# ORD_FV1_2.net
KiCad netlist of a schematic drawn in Altium Designer
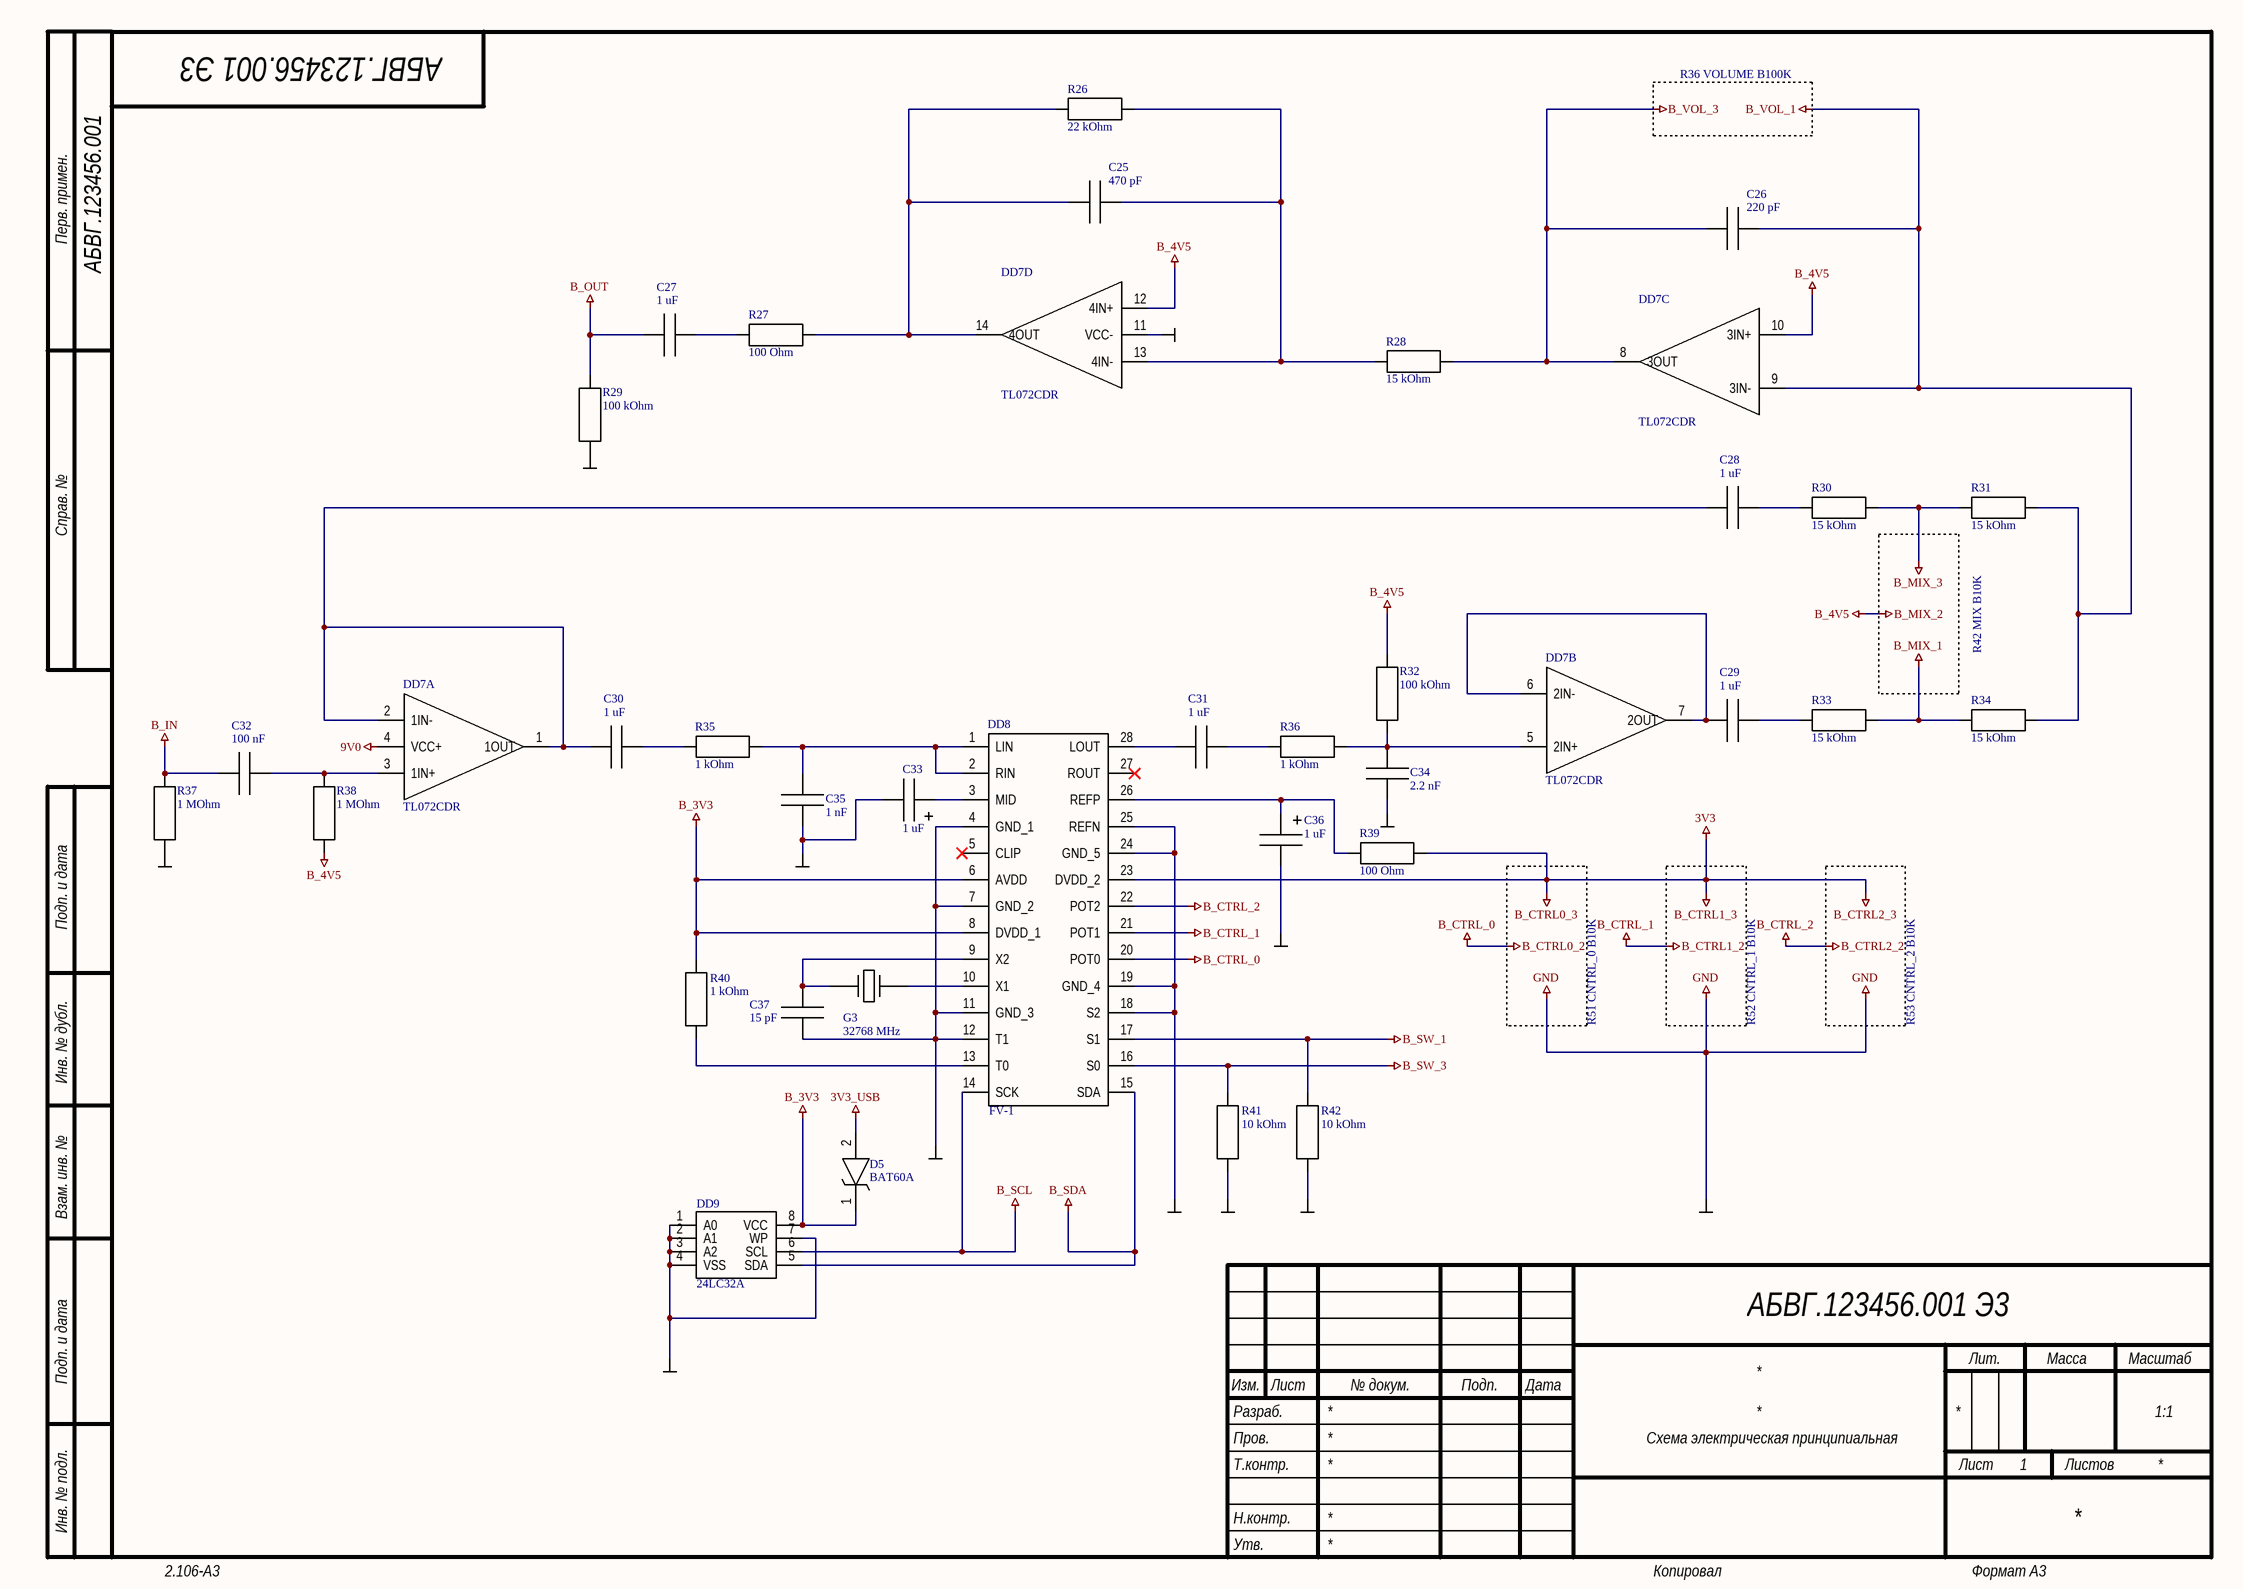
[diagram p0: ORD_FV1_2.SchDoc]

(export (version "E")
  (design (tool "Eeschema 10.0.6"))
  (components
    (comp (ref "C25")
      (value "470 pF")
      (footprint "C0805[2012]")
      (libsource (lib "Gost_passive_lib") (part "Capacitor"))
    )
    (comp (ref "C26")
      (value "220 pF")
      (footprint "C0805[2012]")
      (libsource (lib "Gost_passive_lib") (part "Capacitor"))
    )
    (comp (ref "C27")
      (value "1 uF")
      (footprint "C0805[2012]")
      (libsource (lib "Gost_passive_lib") (part "Capacitor"))
    )
    (comp (ref "C28")
      (value "1 uF")
      (footprint "C0805[2012]")
      (libsource (lib "Gost_passive_lib") (part "Capacitor"))
    )
    (comp (ref "C29")
      (value "1 uF")
      (footprint "C0805[2012]")
      (libsource (lib "Gost_passive_lib") (part "Capacitor"))
    )
    (comp (ref "C30")
      (value "1 uF")
      (footprint "C0805[2012]")
      (libsource (lib "Gost_passive_lib") (part "Capacitor"))
    )
    (comp (ref "C31")
      (value "1 uF")
      (footprint "C0805[2012]")
      (libsource (lib "Gost_passive_lib") (part "Capacitor"))
    )
    (comp (ref "C32")
      (value "100 nF")
      (footprint "C0805[2012]")
      (libsource (lib "Gost_passive_lib") (part "Capacitor"))
    )
    (comp (ref "C33")
      (value "1 uF")
      (footprint "C3216_CASE-A")
      (libsource (lib "Gost_passive_lib") (part "Capacitor_Pol"))
    )
    (comp (ref "C34")
      (value "2.2 nF")
      (footprint "C0805[2012]")
      (libsource (lib "Gost_passive_lib") (part "Capacitor"))
    )
    (comp (ref "C35")
      (value "1 nF")
      (footprint "C0805[2012]")
      (libsource (lib "Gost_passive_lib") (part "Capacitor"))
    )
    (comp (ref "C36")
      (value "1 uF")
      (footprint "C3216_CASE-A")
      (libsource (lib "Gost_passive_lib") (part "Capacitor_Pol"))
    )
    (comp (ref "C37")
      (value "15 pF")
      (footprint "C0805[2012]")
      (libsource (lib "Gost_passive_lib") (part "Capacitor"))
    )
    (comp (ref "D5")
      (value "BAT60A")
      (footprint "SOD323")
      (description "Diode Schottky 10V 3A Automotive 2-Pin SOD-323 T/R")
      (libsource (lib "Gost_passive_lib") (part "BAT60A"))
    )
    (comp (ref "DD7")
      (value "TL072CDR")
      (footprint "SO14")
      (description "TL072CDR, Dual Operational Amplifier 4 MHz -18 to 18V, 8-Pin SO")
      (fields
        (field (name "MANUFACTURER_PART_NUMBER") "LM358DT")
        (field (name "MOUSER PART NUMBER") "511-LM358DT")
      )
      (libsource (lib "Gost_active_libs") (part "TL074CDT"))
    )
    (comp (ref "DD8")
      (value "FV-1")
      (footprint "SOIC28")
      (description "FV-1 Reverb IC, Integrated Stereo ADC & DAC, Integrated Circuit, SOIC-28 300 MIL")
      (fields (field (name "MANUFACTURER_PART_NUMBER") "FV-1 Reverb IC"))
      (libsource (lib "Gost_active_libs") (part "FV-1"))
    )
    (comp (ref "DD9")
      (value "24LC32A")
      (footprint "DIP8_WITH_SOCKET")
      (description "32K I2C Serial EEPROM with Quarter-Array Write-Protect")
      (fields
        (field (name "MANUFACTURER_PART_NUMBER") "24LC32AF-I/P")
        (field (name "MOUSER PART NUMBER") "579-24LC32AF-I/P")
      )
      (libsource (lib "Gost_active_libs") (part "24LC32A"))
    )
    (comp (ref "G3")
      (value "32768 MHz")
      (footprint "HC-49")
      (libsource (lib "Gost_passive_lib") (part "Crystal_2pin"))
    )
    (comp (ref "R26")
      (value "22 kOhm")
      (footprint "R0805[2012]")
      (libsource (lib "Gost_passive_lib") (part "Resistor"))
    )
    (comp (ref "R27")
      (value "100 Ohm")
      (footprint "R0805[2012]")
      (libsource (lib "Gost_passive_lib") (part "Resistor"))
    )
    (comp (ref "R28")
      (value "15 kOhm")
      (footprint "R0805[2012]")
      (libsource (lib "Gost_passive_lib") (part "Resistor"))
    )
    (comp (ref "R29")
      (value "100 kOhm")
      (footprint "R0805[2012]")
      (libsource (lib "Gost_passive_lib") (part "Resistor"))
    )
    (comp (ref "R30")
      (value "15 kOhm")
      (footprint "R0805[2012]")
      (libsource (lib "Gost_passive_lib") (part "Resistor"))
    )
    (comp (ref "R31")
      (value "15 kOhm")
      (footprint "R0805[2012]")
      (libsource (lib "Gost_passive_lib") (part "Resistor"))
    )
    (comp (ref "R32")
      (value "100 kOhm")
      (footprint "R0805[2012]")
      (libsource (lib "Gost_passive_lib") (part "Resistor"))
    )
    (comp (ref "R33")
      (value "15 kOhm")
      (footprint "R0805[2012]")
      (libsource (lib "Gost_passive_lib") (part "Resistor"))
    )
    (comp (ref "R34")
      (value "15 kOhm")
      (footprint "R0805[2012]")
      (libsource (lib "Gost_passive_lib") (part "Resistor"))
    )
    (comp (ref "R35")
      (value "1 kOhm")
      (footprint "R0805[2012]")
      (libsource (lib "Gost_passive_lib") (part "Resistor"))
    )
    (comp (ref "R36")
      (value "1 kOhm")
      (footprint "R0805[2012]")
      (libsource (lib "Gost_passive_lib") (part "Resistor"))
    )
    (comp (ref "R37")
      (value "1 MOhm")
      (footprint "R0805[2012]")
      (libsource (lib "Gost_passive_lib") (part "Resistor"))
    )
    (comp (ref "R38")
      (value "1 MOhm")
      (footprint "R0805[2012]")
      (libsource (lib "Gost_passive_lib") (part "Resistor"))
    )
    (comp (ref "R39")
      (value "100 Ohm")
      (footprint "R0805[2012]")
      (libsource (lib "Gost_passive_lib") (part "Resistor"))
    )
    (comp (ref "R40")
      (value "1 kOhm")
      (footprint "R0805[2012]")
      (libsource (lib "Gost_passive_lib") (part "Resistor"))
    )
    (comp (ref "R41")
      (value "10 kOhm")
      (footprint "R0805[2012]")
      (libsource (lib "Gost_passive_lib") (part "Resistor"))
    )
    (comp (ref "R42")
      (value "10 kOhm")
      (footprint "R0805[2012]")
      (libsource (lib "Gost_passive_lib") (part "Resistor"))
    )
  )
  (nets
    (net (code "1") (name "3V3") (class "Default")
      (node (ref "DD8") (pin "23") (pinfunction "DVDD_2_23") (pintype "passive"))
      (node (ref "R39") (pin "1") (pinfunction "1_1") (pintype "passive"))
    )
    (net (code "2") (name "3V3_USB") (class "Default")
      (node (ref "D5") (pin "2") (pinfunction "A_2") (pintype "passive"))
    )
    (net (code "3") (name "9V0") (class "Default")
      (node (ref "DD7") (pin "4") (pinfunction "VCC+_4") (pintype "power_in"))
    )
    (net (code "4") (name "B_3V3") (class "Default")
      (node (ref "D5") (pin "1") (pinfunction "K_1") (pintype "passive"))
      (node (ref "DD8") (pin "6") (pinfunction "AVDD_6") (pintype "passive"))
      (node (ref "DD8") (pin "8") (pinfunction "DVDD_1_8") (pintype "passive"))
      (node (ref "DD9") (pin "8") (pinfunction "VCC_8") (pintype "passive"))
      (node (ref "R40") (pin "2") (pinfunction "2_2") (pintype "passive"))
    )
    (net (code "5") (name "B_4V5") (class "Default")
      (node (ref "DD7") (pin "10") (pinfunction "3IN+_10") (pintype "passive"))
      (node (ref "DD7") (pin "12") (pinfunction "4IN+_12") (pintype "passive"))
      (node (ref "R32") (pin "1") (pinfunction "1_1") (pintype "passive"))
      (node (ref "R38") (pin "1") (pinfunction "1_1") (pintype "passive"))
    )
    (net (code "6") (name "B_CTRL0_2") (class "Default")
      (node (ref "DD8") (pin "20") (pinfunction "POT0_20") (pintype "passive"))
    )
    (net (code "7") (name "B_CTRL1_2") (class "Default")
      (node (ref "DD8") (pin "21") (pinfunction "POT1_21") (pintype "passive"))
    )
    (net (code "8") (name "B_CTRL2_2") (class "Default")
      (node (ref "DD8") (pin "22") (pinfunction "POT2_22") (pintype "passive"))
    )
    (net (code "9") (name "B_IN") (class "Default")
      (node (ref "C32") (pin "1") (pinfunction "1_1") (pintype "passive"))
      (node (ref "R37") (pin "2") (pinfunction "2_2") (pintype "passive"))
    )
    (net (code "10") (name "B_MIX_1") (class "Default")
      (node (ref "R33") (pin "1") (pinfunction "1_1") (pintype "passive"))
      (node (ref "R34") (pin "2") (pinfunction "2_2") (pintype "passive"))
    )
    (net (code "11") (name "B_MIX_3") (class "Default")
      (node (ref "R30") (pin "1") (pinfunction "1_1") (pintype "passive"))
      (node (ref "R31") (pin "2") (pinfunction "2_2") (pintype "passive"))
    )
    (net (code "12") (name "B_OUT") (class "Default")
      (node (ref "C27") (pin "1") (pinfunction "1_1") (pintype "passive"))
      (node (ref "R29") (pin "2") (pinfunction "2_2") (pintype "passive"))
    )
    (net (code "13") (name "B_SCL") (class "Default")
      (node (ref "DD8") (pin "14") (pinfunction "SCK_14") (pintype "passive"))
      (node (ref "DD9") (pin "6") (pinfunction "SCL_6") (pintype "passive"))
    )
    (net (code "14") (name "B_SDA") (class "Default")
      (node (ref "DD8") (pin "15") (pinfunction "SDA_15") (pintype "passive"))
      (node (ref "DD9") (pin "5") (pinfunction "SDA_5") (pintype "passive"))
    )
    (net (code "15") (name "B_SW_1") (class "Default")
      (node (ref "DD8") (pin "17") (pinfunction "S1_17") (pintype "passive"))
      (node (ref "R42") (pin "2") (pinfunction "2_2") (pintype "passive"))
    )
    (net (code "16") (name "B_SW_3") (class "Default")
      (node (ref "DD8") (pin "16") (pinfunction "S0_16") (pintype "passive"))
      (node (ref "R41") (pin "2") (pinfunction "2_2") (pintype "passive"))
    )
    (net (code "17") (name "B_VOL_1") (class "Default")
      (node (ref "C26") (pin "2") (pinfunction "2_2") (pintype "passive"))
      (node (ref "DD7") (pin "9") (pinfunction "3IN-_9") (pintype "passive"))
      (node (ref "R31") (pin "1") (pinfunction "1_1") (pintype "passive"))
      (node (ref "R34") (pin "1") (pinfunction "1_1") (pintype "passive"))
    )
    (net (code "18") (name "B_VOL_3") (class "Default")
      (node (ref "C26") (pin "1") (pinfunction "1_1") (pintype "passive"))
      (node (ref "DD7") (pin "8") (pinfunction "3OUT_8") (pintype "passive"))
      (node (ref "R28") (pin "1") (pinfunction "1_1") (pintype "passive"))
    )
    (net (code "19") (name "GND") (class "Default")
      (node (ref "C33") (pin "2") (pinfunction "2_2") (pintype "passive"))
      (node (ref "C34") (pin "1") (pinfunction "1_1") (pintype "passive"))
      (node (ref "C35") (pin "1") (pinfunction "1_1") (pintype "passive"))
      (node (ref "C36") (pin "2") (pinfunction "2_2") (pintype "passive"))
      (node (ref "C37") (pin "2") (pinfunction "2_2") (pintype "passive"))
      (node (ref "DD7") (pin "11") (pinfunction "VCC-_11") (pintype "power_in"))
      (node (ref "DD8") (pin "11") (pinfunction "GND_3_11") (pintype "passive"))
      (node (ref "DD8") (pin "12") (pinfunction "T1_12") (pintype "passive"))
      (node (ref "DD8") (pin "18") (pinfunction "S2_18") (pintype "passive"))
      (node (ref "DD8") (pin "19") (pinfunction "GND_4_19") (pintype "passive"))
      (node (ref "DD8") (pin "24") (pinfunction "GND_5_24") (pintype "passive"))
      (node (ref "DD8") (pin "25") (pinfunction "REFN_25") (pintype "passive"))
      (node (ref "DD8") (pin "4") (pinfunction "GND_1_4") (pintype "passive"))
      (node (ref "DD8") (pin "7") (pinfunction "GND_2_7") (pintype "passive"))
      (node (ref "DD9") (pin "1") (pinfunction "A0_1") (pintype "passive"))
      (node (ref "DD9") (pin "2") (pinfunction "A1_2") (pintype "passive"))
      (node (ref "DD9") (pin "3") (pinfunction "A2_3") (pintype "passive"))
      (node (ref "DD9") (pin "4") (pinfunction "VSS_4") (pintype "passive"))
      (node (ref "DD9") (pin "7") (pinfunction "WP_7") (pintype "passive"))
      (node (ref "R29") (pin "1") (pinfunction "1_1") (pintype "passive"))
      (node (ref "R37") (pin "1") (pinfunction "1_1") (pintype "passive"))
      (node (ref "R41") (pin "1") (pinfunction "1_1") (pintype "passive"))
      (node (ref "R42") (pin "1") (pinfunction "1_1") (pintype "passive"))
    )
    (net (code "20") (name "Net-(C27-Pad2)") (class "Default")
      (node (ref "C27") (pin "2") (pinfunction "2_2") (pintype "passive"))
      (node (ref "R27") (pin "2") (pinfunction "2_2") (pintype "passive"))
    )
    (net (code "21") (name "Net-(C28-Pad2)") (class "Default")
      (node (ref "C28") (pin "2") (pinfunction "2_2") (pintype "passive"))
      (node (ref "R30") (pin "2") (pinfunction "2_2") (pintype "passive"))
    )
    (net (code "22") (name "Net-(C29-Pad2)") (class "Default")
      (node (ref "C29") (pin "2") (pinfunction "2_2") (pintype "passive"))
      (node (ref "R33") (pin "2") (pinfunction "2_2") (pintype "passive"))
    )
    (net (code "23") (name "Net-(C30-Pad2)") (class "Default")
      (node (ref "C30") (pin "2") (pinfunction "2_2") (pintype "passive"))
      (node (ref "R35") (pin "2") (pinfunction "2_2") (pintype "passive"))
    )
    (net (code "24") (name "Net-(C31-Pad2)") (class "Default")
      (node (ref "C31") (pin "2") (pinfunction "2_2") (pintype "passive"))
      (node (ref "R36") (pin "2") (pinfunction "2_2") (pintype "passive"))
    )
    (net (code "25") (name "Net-(DD7A-1IN+)") (class "Default")
      (node (ref "C32") (pin "2") (pinfunction "2_2") (pintype "passive"))
      (node (ref "DD7") (pin "3") (pinfunction "1IN+_3") (pintype "passive"))
      (node (ref "R38") (pin "2") (pinfunction "2_2") (pintype "passive"))
    )
    (net (code "26") (name "Net-(DD7A-1IN-)") (class "Default")
      (node (ref "C28") (pin "1") (pinfunction "1_1") (pintype "passive"))
      (node (ref "C30") (pin "1") (pinfunction "1_1") (pintype "passive"))
      (node (ref "DD7") (pin "1") (pinfunction "1OUT_1") (pintype "passive"))
      (node (ref "DD7") (pin "2") (pinfunction "1IN-_2") (pintype "passive"))
    )
    (net (code "27") (name "Net-(DD7B-2IN+)") (class "Default")
      (node (ref "C34") (pin "2") (pinfunction "2_2") (pintype "passive"))
      (node (ref "DD7") (pin "5") (pinfunction "2IN+_5") (pintype "passive"))
      (node (ref "R32") (pin "2") (pinfunction "2_2") (pintype "passive"))
      (node (ref "R36") (pin "1") (pinfunction "1_1") (pintype "passive"))
    )
    (net (code "28") (name "Net-(DD7B-2IN-)") (class "Default")
      (node (ref "C29") (pin "1") (pinfunction "1_1") (pintype "passive"))
      (node (ref "DD7") (pin "6") (pinfunction "2IN-_6") (pintype "passive"))
      (node (ref "DD7") (pin "7") (pinfunction "2OUT_7") (pintype "passive"))
    )
    (net (code "29") (name "Net-(DD7D-4IN-)") (class "Default")
      (node (ref "C25") (pin "2") (pinfunction "2_2") (pintype "passive"))
      (node (ref "DD7") (pin "13") (pinfunction "4IN-_13") (pintype "passive"))
      (node (ref "R26") (pin "1") (pinfunction "1_1") (pintype "passive"))
      (node (ref "R28") (pin "2") (pinfunction "2_2") (pintype "passive"))
    )
    (net (code "30") (name "Net-(DD7D-4OUT)") (class "Default")
      (node (ref "C25") (pin "1") (pinfunction "1_1") (pintype "passive"))
      (node (ref "DD7") (pin "14") (pinfunction "4OUT_14") (pintype "passive"))
      (node (ref "R26") (pin "2") (pinfunction "2_2") (pintype "passive"))
      (node (ref "R27") (pin "1") (pinfunction "1_1") (pintype "passive"))
    )
    (net (code "31") (name "Net-(DD8-LIN)") (class "Default")
      (node (ref "C35") (pin "2") (pinfunction "2_2") (pintype "passive"))
      (node (ref "DD8") (pin "1") (pinfunction "LIN_1") (pintype "passive"))
      (node (ref "DD8") (pin "2") (pinfunction "RIN_2") (pintype "passive"))
      (node (ref "R35") (pin "1") (pinfunction "1_1") (pintype "passive"))
    )
    (net (code "32") (name "Net-(DD8-LOUT)") (class "Default")
      (node (ref "C31") (pin "1") (pinfunction "1_1") (pintype "passive"))
      (node (ref "DD8") (pin "28") (pinfunction "LOUT_28") (pintype "passive"))
    )
    (net (code "33") (name "Net-(DD8-MID)") (class "Default")
      (node (ref "C33") (pin "1") (pinfunction "1_1") (pintype "passive"))
      (node (ref "DD8") (pin "3") (pinfunction "MID_3") (pintype "passive"))
    )
    (net (code "34") (name "Net-(DD8-REFP)") (class "Default")
      (node (ref "C36") (pin "1") (pinfunction "1_1") (pintype "passive"))
      (node (ref "DD8") (pin "26") (pinfunction "REFP_26") (pintype "passive"))
      (node (ref "R39") (pin "2") (pinfunction "2_2") (pintype "passive"))
    )
    (net (code "35") (name "Net-(DD8-T0)") (class "Default")
      (node (ref "DD8") (pin "13") (pinfunction "T0_13") (pintype "passive"))
      (node (ref "R40") (pin "1") (pinfunction "1_1") (pintype "passive"))
    )
    (net (code "36") (name "Net-(DD8-X1)") (class "Default")
      (node (ref "DD8") (pin "10") (pinfunction "X1_10") (pintype "passive"))
      (node (ref "G3") (pin "2") (pinfunction "2_2") (pintype "passive"))
    )
    (net (code "37") (name "Net-(DD8-X2)") (class "Default")
      (node (ref "C37") (pin "1") (pinfunction "1_1") (pintype "passive"))
      (node (ref "DD8") (pin "9") (pinfunction "X2_9") (pintype "passive"))
      (node (ref "G3") (pin "1") (pinfunction "1_1") (pintype "passive"))
    )
    (net (code "38") (name "unconnected-(DD8-CLIP-Pad5)") (class "Default")
      (node (ref "DD8") (pin "5") (pinfunction "CLIP_5") (pintype "passive+no_connect"))
    )
    (net (code "39") (name "unconnected-(DD8-ROUT-Pad27)") (class "Default")
      (node (ref "DD8") (pin "27") (pinfunction "ROUT_27") (pintype "passive+no_connect"))
    )
  )
)
